# LED.net
KiCad netlist of a schematic drawn in Altium Designer
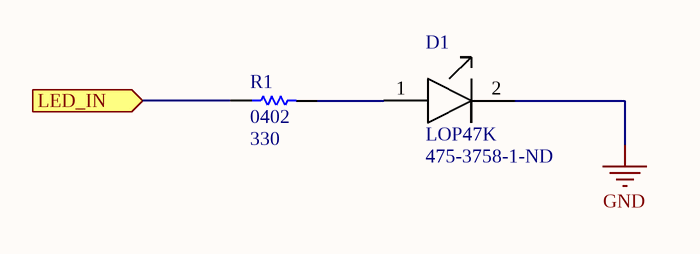
[diagram p0: LED.SchDoc]

(export (version "E")
  (design (tool "Eeschema 10.0.6"))
  (components
    (comp (ref "D1")
      (value "LOP47K")
      (footprint "LB P4SG")
      (description "LED ORANGE CLEAR SMD BOTTOM ENTRY")
      (fields (field (name "SUPPLIER PART NUMBER 1") "475-3758-1-ND"))
      (libsource (lib "heron-general") (part "LO P47K"))
    )
    (comp (ref "R1")
      (value "0402")
      (footprint "RES0402R")
      (description "0402 resistor")
      (fields
        (field (name "ALTIUM_VALUE") "330")
        (field (name "MANUFACTURER") "TE Connectivity")
        (field (name "MANUFACTURER PART NUMBER") "CRGCQ0402F330R")
      )
      (libsource (lib "heron-general") (part "RES0402"))
    )
  )
  (nets
    (net (code "1") (name "/LED_IN") (class "Default")
      (node (ref "R1") (pin "1") (pinfunction "1_1") (pintype "passive"))
    )
    (net (code "2") (name "GND") (class "Default")
      (node (ref "D1") (pin "2") (pinfunction "Cathode_2") (pintype "passive"))
    )
    (net (code "3") (name "Net-(D1-Anode)") (class "Default")
      (node (ref "D1") (pin "1") (pinfunction "Anode_1") (pintype "passive"))
      (node (ref "R1") (pin "2") (pinfunction "2_2") (pintype "passive"))
    )
  )
)
